# Gate_Driver.net
KiCad netlist of a schematic drawn in Altium Designer
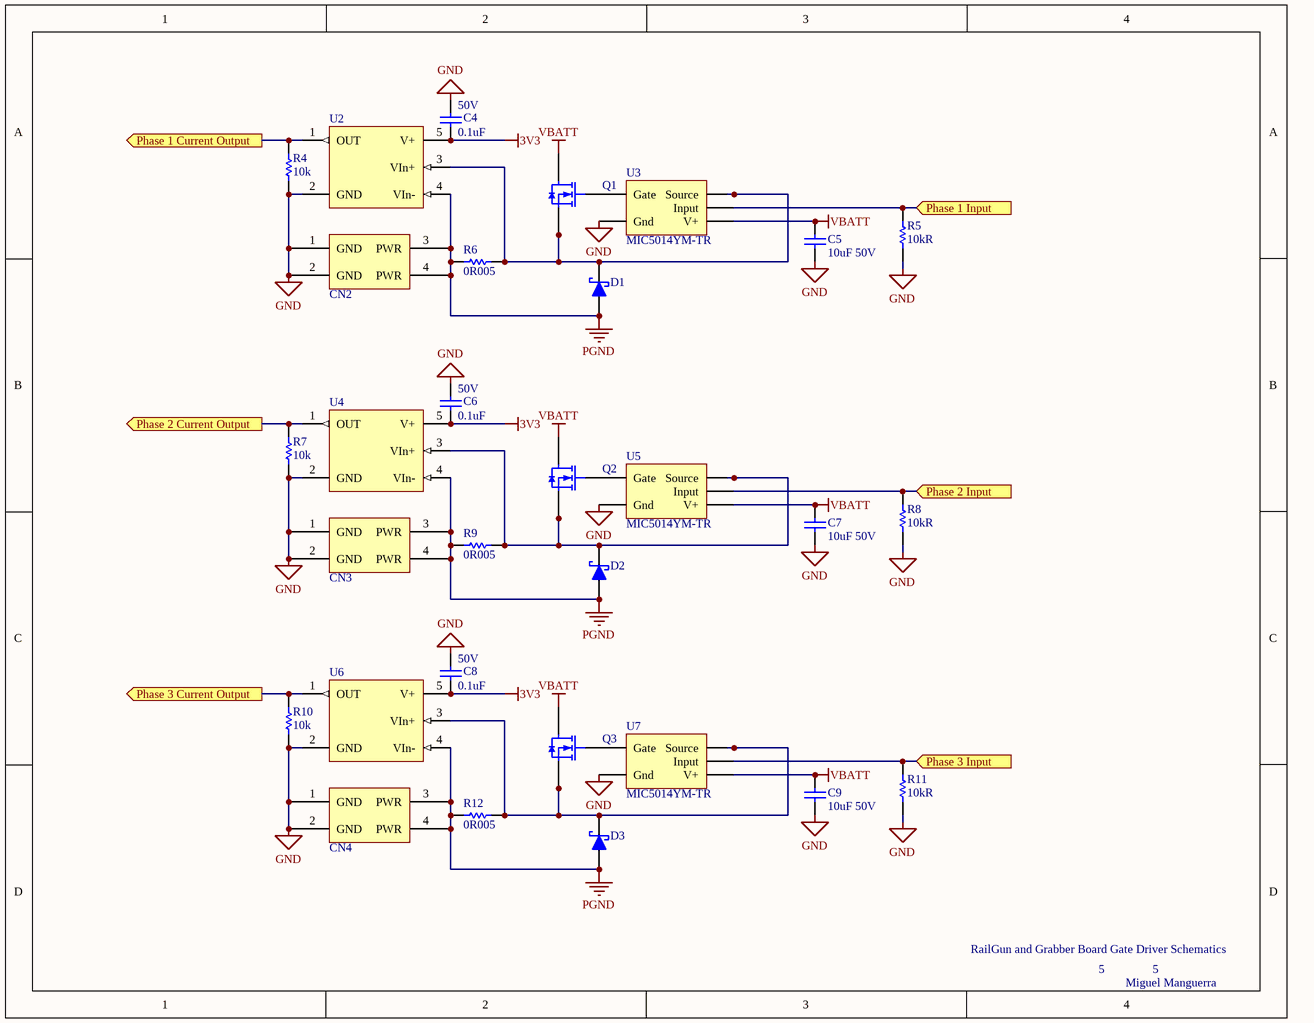
[diagram p0: Gate Driver.SchDoc]

(export (version "E")
  (design (tool "Eeschema 10.0.6"))
  (components
    (comp (ref "C4")
      (value "CL10B104JB8NNNC")
      (footprint "FP-CL10-0_1-MFG")
      (description "CAP CER 0.1UF 50V X7R 0603")
      (fields
        (field (name "TOLERANCE") "5%")
        (field (name "VOLTAGE") "50V")
        (field (name "CAPACITANCE") "0.1uF")
      )
      (libsource (lib "AUVIC") (part "CAP-NP-2"))
    )
    (comp (ref "C5")
      (value "10uF 50V")
      (footprint "CAPC3216N(1206\")")
      (description "Capacitor, Ceramic, 50V, +/- 10%, 1206 SMD, X5R")
      (fields (field (name "PUBLISHER") "AUVic"))
      (libsource (lib "") (part "Symbol_1"))
    )
    (comp (ref "C6")
      (value "CL10B104JB8NNNC")
      (footprint "FP-CL10-0_1-MFG")
      (description "CAP CER 0.1UF 50V X7R 0603")
      (fields
        (field (name "TOLERANCE") "5%")
        (field (name "VOLTAGE") "50V")
        (field (name "CAPACITANCE") "0.1uF")
      )
      (libsource (lib "AUVIC") (part "CAP-NP-2"))
    )
    (comp (ref "C7")
      (value "10uF 50V")
      (footprint "CAPC3216N(1206\")")
      (description "Capacitor, Ceramic, 50V, +/- 10%, 1206 SMD, X5R")
      (fields (field (name "PUBLISHER") "AUVic"))
      (libsource (lib "") (part "Symbol_1"))
    )
    (comp (ref "C8")
      (value "CL10B104JB8NNNC")
      (footprint "FP-CL10-0_1-MFG")
      (description "CAP CER 0.1UF 50V X7R 0603")
      (fields
        (field (name "TOLERANCE") "5%")
        (field (name "VOLTAGE") "50V")
        (field (name "CAPACITANCE") "0.1uF")
      )
      (libsource (lib "AUVIC") (part "CAP-NP-2"))
    )
    (comp (ref "C9")
      (value "10uF 50V")
      (footprint "CAPC3216N(1206\")")
      (description "Capacitor, Ceramic, 50V, +/- 10%, 1206 SMD, X5R")
      (fields (field (name "PUBLISHER") "AUVic"))
      (libsource (lib "") (part "Symbol_1"))
    )
    (comp (ref "CN2")
      (value "Header, Female, 2x2, RIght Angle, Pitch: 0.118\"  (3.00mm), THT")
      (footprint "2x2 Pitch 118mil connector")
      (description "Connector Header Through Hole, Right Angle 4 position 0.118\" (3.00mm)")
      (fields (field (name "CREATED BY") "Poorna Chander Kalidas") (field (name "PUBLISHER") "AUVic"))
      (libsource (lib "AUVIC") (part "Header, Female, 2x2, RIght Angle, Pitch{colon} 0.118{dblquote}  (3.00mm), THT"))
    )
    (comp (ref "CN3")
      (value "Header, Female, 2x2, RIght Angle, Pitch: 0.118\"  (3.00mm), THT")
      (footprint "2x2 Pitch 118mil connector")
      (description "Connector Header Through Hole, Right Angle 4 position 0.118\" (3.00mm)")
      (fields (field (name "CREATED BY") "Poorna Chander Kalidas") (field (name "PUBLISHER") "AUVic"))
      (libsource (lib "AUVIC") (part "Header, Female, 2x2, RIght Angle, Pitch{colon} 0.118{dblquote}  (3.00mm), THT"))
    )
    (comp (ref "CN4")
      (value "Header, Female, 2x2, RIght Angle, Pitch: 0.118\"  (3.00mm), THT")
      (footprint "2x2 Pitch 118mil connector")
      (description "Connector Header Through Hole, Right Angle 4 position 0.118\" (3.00mm)")
      (fields (field (name "CREATED BY") "Poorna Chander Kalidas") (field (name "PUBLISHER") "AUVic"))
      (libsource (lib "AUVIC") (part "Header, Female, 2x2, RIght Angle, Pitch{colon} 0.118{dblquote}  (3.00mm), THT"))
    )
    (comp (ref "D1")
      (value "TSSA5U50E3GCT-ND")
      (footprint "DO-214AC")
      (description "Diode Schottky 50V 5A Surface Mount DO-214AC (SMA)")
      (fields (field (name "CREATED BY") "Poorna Chander Kalidas"))
      (libsource (lib "AUVIC") (part "TSSA5U50E3GCT-ND"))
    )
    (comp (ref "D2")
      (value "TSSA5U50E3GCT-ND")
      (footprint "DO-214AC")
      (description "Diode Schottky 50V 5A Surface Mount DO-214AC (SMA)")
      (fields (field (name "CREATED BY") "Poorna Chander Kalidas"))
      (libsource (lib "AUVIC") (part "TSSA5U50E3GCT-ND"))
    )
    (comp (ref "D3")
      (value "TSSA5U50E3GCT-ND")
      (footprint "DO-214AC")
      (description "Diode Schottky 50V 5A Surface Mount DO-214AC (SMA)")
      (fields (field (name "CREATED BY") "Poorna Chander Kalidas"))
      (libsource (lib "AUVIC") (part "TSSA5U50E3GCT-ND"))
    )
    (comp (ref "Q1")
      (value "MOSFET N-Channel")
      (footprint "LFPAK-PowerSO8")
      (description "MOSFET N-Channel, 40V, 100A, 272W, Enh-Mode")
      (fields
        (field (name "MFG") "NXP Semiconductors")
        (field (name "PUBLISHER") "AUVic")
        (field (name "CREATED BY") "Ashwin Sira")
        (field (name "REVIEWED_BY") "Ashwin Sira")
      )
      (libsource (lib "AUVIC") (part "MOSFET N-Channel, 40V, 100A, 272W"))
    )
    (comp (ref "Q2")
      (value "MOSFET N-Channel")
      (footprint "LFPAK-PowerSO8")
      (description "MOSFET N-Channel, 40V, 100A, 272W, Enh-Mode")
      (fields
        (field (name "MFG") "NXP Semiconductors")
        (field (name "PUBLISHER") "AUVic")
        (field (name "CREATED BY") "Ashwin Sira")
        (field (name "REVIEWED_BY") "Ashwin Sira")
      )
      (libsource (lib "AUVIC") (part "MOSFET N-Channel, 40V, 100A, 272W"))
    )
    (comp (ref "Q3")
      (value "MOSFET N-Channel")
      (footprint "LFPAK-PowerSO8")
      (description "MOSFET N-Channel, 40V, 100A, 272W, Enh-Mode")
      (fields
        (field (name "MFG") "NXP Semiconductors")
        (field (name "PUBLISHER") "AUVic")
        (field (name "CREATED BY") "Ashwin Sira")
        (field (name "REVIEWED_BY") "Ashwin Sira")
      )
      (libsource (lib "AUVIC") (part "MOSFET N-Channel, 40V, 100A, 272W"))
    )
    (comp (ref "R4")
      (value "10k")
      (footprint "RESC1608N(0603\")")
      (description "10kR, 1%, 1/10W, 0603 SMD")
      (fields (field (name "MADE BY") "Ashwin Sira"))
      (libsource (lib "AUVIC") (part "Symbol"))
    )
    (comp (ref "R5")
      (value "10kR")
      (footprint "RESC1608N(0603\")")
      (description "10kR, 1%, 1/10W, 0603 SMD")
      (fields (field (name "MADE BY") "Ashwin Sira"))
      (libsource (lib "AUVIC") (part "Symbol"))
    )
    (comp (ref "R6")
      (value "0R005")
      (footprint "RESC6332N(2512\")")
      (description "0R005, 1%, 3W, 2512 SMD")
      (fields
        (field (name "MFG") "Riedon")
        (field (name "CREATED BY") "Andy Bates")
        (field (name "PUBLISHER") "AUVic")
      )
      (libsource (lib "AUVIC") (part "Symbol"))
    )
    (comp (ref "R7")
      (value "10k")
      (footprint "RESC1608N(0603\")")
      (description "10kR, 1%, 1/10W, 0603 SMD")
      (fields (field (name "MADE BY") "Ashwin Sira"))
      (libsource (lib "AUVIC") (part "Symbol"))
    )
    (comp (ref "R8")
      (value "10kR")
      (footprint "RESC1608N(0603\")")
      (description "10kR, 1%, 1/10W, 0603 SMD")
      (fields (field (name "MADE BY") "Ashwin Sira"))
      (libsource (lib "AUVIC") (part "Symbol"))
    )
    (comp (ref "R9")
      (value "0R005")
      (footprint "RESC6332N(2512\")")
      (description "0R005, 1%, 3W, 2512 SMD")
      (fields
        (field (name "MFG") "Riedon")
        (field (name "CREATED BY") "Andy Bates")
        (field (name "PUBLISHER") "AUVic")
      )
      (libsource (lib "AUVIC") (part "Symbol"))
    )
    (comp (ref "R10")
      (value "10k")
      (footprint "RESC1608N(0603\")")
      (description "10kR, 1%, 1/10W, 0603 SMD")
      (fields (field (name "MADE BY") "Ashwin Sira"))
      (libsource (lib "AUVIC") (part "Symbol"))
    )
    (comp (ref "R11")
      (value "10kR")
      (footprint "RESC1608N(0603\")")
      (description "10kR, 1%, 1/10W, 0603 SMD")
      (fields (field (name "MADE BY") "Ashwin Sira"))
      (libsource (lib "AUVIC") (part "Symbol"))
    )
    (comp (ref "R12")
      (value "0R005")
      (footprint "RESC6332N(2512\")")
      (description "0R005, 1%, 3W, 2512 SMD")
      (fields
        (field (name "MFG") "Riedon")
        (field (name "CREATED BY") "Andy Bates")
        (field (name "PUBLISHER") "AUVic")
      )
      (libsource (lib "AUVIC") (part "Symbol"))
    )
    (comp (ref "U2")
      (value "INA168, Current Sensor, High-Side, Analog")
      (footprint "SOT23-5")
      (fields (field (name "CREATED BY") "Jacob Lower") (field (name "PUBLISHER") "AUVic"))
      (libsource (lib "AUVIC") (part "INA168, Current Sensor, High-Side, Analog"))
    )
    (comp (ref "U3")
      (value "MIC5014YM-TR")
      (footprint "SOC 8")
      (description "High-Side or Low-Side Gate Driver IC Non-Inverting 8-SOIC")
      (libsource (lib "AUVIC") (part "Gate Driver TTL Logic 3 - 30V"))
    )
    (comp (ref "U4")
      (value "INA168, Current Sensor, High-Side, Analog")
      (footprint "SOT23-5")
      (fields (field (name "CREATED BY") "Jacob Lower") (field (name "PUBLISHER") "AUVic"))
      (libsource (lib "AUVIC") (part "INA168, Current Sensor, High-Side, Analog"))
    )
    (comp (ref "U5")
      (value "MIC5014YM-TR")
      (footprint "SOC 8")
      (description "High-Side or Low-Side Gate Driver IC Non-Inverting 8-SOIC")
      (libsource (lib "AUVIC") (part "Gate Driver TTL Logic 3 - 30V"))
    )
    (comp (ref "U6")
      (value "INA168, Current Sensor, High-Side, Analog")
      (footprint "SOT23-5")
      (fields (field (name "CREATED BY") "Jacob Lower") (field (name "PUBLISHER") "AUVic"))
      (libsource (lib "AUVIC") (part "INA168, Current Sensor, High-Side, Analog"))
    )
    (comp (ref "U7")
      (value "MIC5014YM-TR")
      (footprint "SOC 8")
      (description "High-Side or Low-Side Gate Driver IC Non-Inverting 8-SOIC")
      (libsource (lib "AUVIC") (part "Gate Driver TTL Logic 3 - 30V"))
    )
  )
  (nets
    (net (code "1") (name "/Phase 1 Current Output") (class "Default")
      (node (ref "R4") (pin "2") (pinfunction "2_2") (pintype "passive"))
      (node (ref "U2") (pin "1") (pinfunction "OUT_1") (pintype "output"))
    )
    (net (code "2") (name "/Phase 1 Input") (class "Default")
      (node (ref "R5") (pin "1") (pinfunction "1_1") (pintype "passive"))
      (node (ref "U3") (pin "2") (pinfunction "Input_2") (pintype "passive"))
    )
    (net (code "3") (name "/Phase 2 Current Output") (class "Default")
      (node (ref "R7") (pin "2") (pinfunction "2_2") (pintype "passive"))
      (node (ref "U4") (pin "1") (pinfunction "OUT_1") (pintype "output"))
    )
    (net (code "4") (name "/Phase 2 Input") (class "Default")
      (node (ref "R8") (pin "1") (pinfunction "1_1") (pintype "passive"))
      (node (ref "U5") (pin "2") (pinfunction "Input_2") (pintype "passive"))
    )
    (net (code "5") (name "/Phase 3 Current Output") (class "Default")
      (node (ref "R10") (pin "2") (pinfunction "2_2") (pintype "passive"))
      (node (ref "U6") (pin "1") (pinfunction "OUT_1") (pintype "output"))
    )
    (net (code "6") (name "/Phase 3 Input") (class "Default")
      (node (ref "R11") (pin "1") (pinfunction "1_1") (pintype "passive"))
      (node (ref "U7") (pin "2") (pinfunction "Input_2") (pintype "passive"))
    )
    (net (code "7") (name "3V3") (class "Default")
      (node (ref "C4") (pin "2") (pinfunction "2_2") (pintype "passive"))
      (node (ref "C6") (pin "2") (pinfunction "2_2") (pintype "passive"))
      (node (ref "C8") (pin "2") (pinfunction "2_2") (pintype "passive"))
      (node (ref "U2") (pin "5") (pinfunction "V+_5") (pintype "power_in"))
      (node (ref "U4") (pin "5") (pinfunction "V+_5") (pintype "power_in"))
      (node (ref "U6") (pin "5") (pinfunction "V+_5") (pintype "power_in"))
    )
    (net (code "8") (name "GND") (class "Default")
      (node (ref "C4") (pin "1") (pinfunction "1_1") (pintype "passive"))
      (node (ref "C5") (pin "2") (pinfunction "Cathode_2") (pintype "passive"))
      (node (ref "C6") (pin "1") (pinfunction "1_1") (pintype "passive"))
      (node (ref "C7") (pin "2") (pinfunction "Cathode_2") (pintype "passive"))
      (node (ref "C8") (pin "1") (pinfunction "1_1") (pintype "passive"))
      (node (ref "C9") (pin "2") (pinfunction "Cathode_2") (pintype "passive"))
      (node (ref "CN2") (pin "1") (pinfunction "GND_1") (pintype "passive"))
      (node (ref "CN2") (pin "2") (pinfunction "GND_2") (pintype "passive"))
      (node (ref "CN3") (pin "1") (pinfunction "GND_1") (pintype "passive"))
      (node (ref "CN3") (pin "2") (pinfunction "GND_2") (pintype "passive"))
      (node (ref "CN4") (pin "1") (pinfunction "GND_1") (pintype "passive"))
      (node (ref "CN4") (pin "2") (pinfunction "GND_2") (pintype "passive"))
      (node (ref "R10") (pin "1") (pinfunction "1_1") (pintype "passive"))
      (node (ref "R11") (pin "2") (pinfunction "2_2") (pintype "passive"))
      (node (ref "R4") (pin "1") (pinfunction "1_1") (pintype "passive"))
      (node (ref "R5") (pin "2") (pinfunction "2_2") (pintype "passive"))
      (node (ref "R7") (pin "1") (pinfunction "1_1") (pintype "passive"))
      (node (ref "R8") (pin "2") (pinfunction "2_2") (pintype "passive"))
      (node (ref "U2") (pin "2") (pinfunction "GND_2") (pintype "power_in"))
      (node (ref "U3") (pin "4") (pinfunction "Gnd_4") (pintype "passive"))
      (node (ref "U4") (pin "2") (pinfunction "GND_2") (pintype "power_in"))
      (node (ref "U5") (pin "4") (pinfunction "Gnd_4") (pintype "passive"))
      (node (ref "U6") (pin "2") (pinfunction "GND_2") (pintype "power_in"))
      (node (ref "U7") (pin "4") (pinfunction "Gnd_4") (pintype "passive"))
    )
    (net (code "9") (name "Net-(D1-Cathode)") (class "Default")
      (node (ref "D1") (pin "2") (pinfunction "Cathode_2") (pintype "passive"))
      (node (ref "Q1") (pin "1") (pinfunction "Source_1") (pintype "power_in"))
      (node (ref "Q1") (pin "2") (pinfunction "Source_2") (pintype "power_in"))
      (node (ref "Q1") (pin "3") (pinfunction "Source_3") (pintype "power_in"))
      (node (ref "R6") (pin "2") (pinfunction "2_2") (pintype "passive"))
      (node (ref "U2") (pin "3") (pinfunction "VIn+_3") (pintype "input"))
      (node (ref "U3") (pin "3") (pinfunction "Source_3") (pintype "passive"))
    )
    (net (code "10") (name "Net-(D2-Cathode)") (class "Default")
      (node (ref "D2") (pin "2") (pinfunction "Cathode_2") (pintype "passive"))
      (node (ref "Q2") (pin "1") (pinfunction "Source_1") (pintype "power_in"))
      (node (ref "Q2") (pin "2") (pinfunction "Source_2") (pintype "power_in"))
      (node (ref "Q2") (pin "3") (pinfunction "Source_3") (pintype "power_in"))
      (node (ref "R9") (pin "2") (pinfunction "2_2") (pintype "passive"))
      (node (ref "U4") (pin "3") (pinfunction "VIn+_3") (pintype "input"))
      (node (ref "U5") (pin "3") (pinfunction "Source_3") (pintype "passive"))
    )
    (net (code "11") (name "Net-(D3-Cathode)") (class "Default")
      (node (ref "D3") (pin "2") (pinfunction "Cathode_2") (pintype "passive"))
      (node (ref "Q3") (pin "1") (pinfunction "Source_1") (pintype "power_in"))
      (node (ref "Q3") (pin "2") (pinfunction "Source_2") (pintype "power_in"))
      (node (ref "Q3") (pin "3") (pinfunction "Source_3") (pintype "power_in"))
      (node (ref "R12") (pin "2") (pinfunction "2_2") (pintype "passive"))
      (node (ref "U6") (pin "3") (pinfunction "VIn+_3") (pintype "input"))
      (node (ref "U7") (pin "3") (pinfunction "Source_3") (pintype "passive"))
    )
    (net (code "12") (name "Net-(Q1-Gate)") (class "Default")
      (node (ref "Q1") (pin "4") (pinfunction "Gate_4") (pintype "power_in"))
      (node (ref "U3") (pin "5") (pinfunction "Gate_5") (pintype "passive"))
    )
    (net (code "13") (name "Net-(Q2-Gate)") (class "Default")
      (node (ref "Q2") (pin "4") (pinfunction "Gate_4") (pintype "power_in"))
      (node (ref "U5") (pin "5") (pinfunction "Gate_5") (pintype "passive"))
    )
    (net (code "14") (name "Net-(Q3-Gate)") (class "Default")
      (node (ref "Q3") (pin "4") (pinfunction "Gate_4") (pintype "power_in"))
      (node (ref "U7") (pin "5") (pinfunction "Gate_5") (pintype "passive"))
    )
    (net (code "15") (name "PGND") (class "Default")
      (node (ref "CN2") (pin "3") (pinfunction "PWR_3") (pintype "passive"))
      (node (ref "CN2") (pin "4") (pinfunction "PWR_4") (pintype "passive"))
      (node (ref "CN3") (pin "3") (pinfunction "PWR_3") (pintype "passive"))
      (node (ref "CN3") (pin "4") (pinfunction "PWR_4") (pintype "passive"))
      (node (ref "CN4") (pin "3") (pinfunction "PWR_3") (pintype "passive"))
      (node (ref "CN4") (pin "4") (pinfunction "PWR_4") (pintype "passive"))
      (node (ref "D1") (pin "1") (pinfunction "Anode_1") (pintype "passive"))
      (node (ref "D2") (pin "1") (pinfunction "Anode_1") (pintype "passive"))
      (node (ref "D3") (pin "1") (pinfunction "Anode_1") (pintype "passive"))
      (node (ref "R12") (pin "1") (pinfunction "1_1") (pintype "passive"))
      (node (ref "R6") (pin "1") (pinfunction "1_1") (pintype "passive"))
      (node (ref "R9") (pin "1") (pinfunction "1_1") (pintype "passive"))
      (node (ref "U2") (pin "4") (pinfunction "VIn-_4") (pintype "input"))
      (node (ref "U4") (pin "4") (pinfunction "VIn-_4") (pintype "input"))
      (node (ref "U6") (pin "4") (pinfunction "VIn-_4") (pintype "input"))
    )
    (net (code "16") (name "VBATT") (class "Default")
      (node (ref "C5") (pin "1") (pinfunction "Anode_1") (pintype "passive"))
      (node (ref "C7") (pin "1") (pinfunction "Anode_1") (pintype "passive"))
      (node (ref "C9") (pin "1") (pinfunction "Anode_1") (pintype "passive"))
      (node (ref "Q1") (pin "5") (pinfunction "Drain_5") (pintype "power_in"))
      (node (ref "Q2") (pin "5") (pinfunction "Drain_5") (pintype "power_in"))
      (node (ref "Q3") (pin "5") (pinfunction "Drain_5") (pintype "power_in"))
      (node (ref "U3") (pin "1") (pinfunction "V+_1") (pintype "passive"))
      (node (ref "U5") (pin "1") (pinfunction "V+_1") (pintype "passive"))
      (node (ref "U7") (pin "1") (pinfunction "V+_1") (pintype "passive"))
    )
  )
)
